# SkateRemote.net
KiCad netlist of a schematic drawn in EAGLE
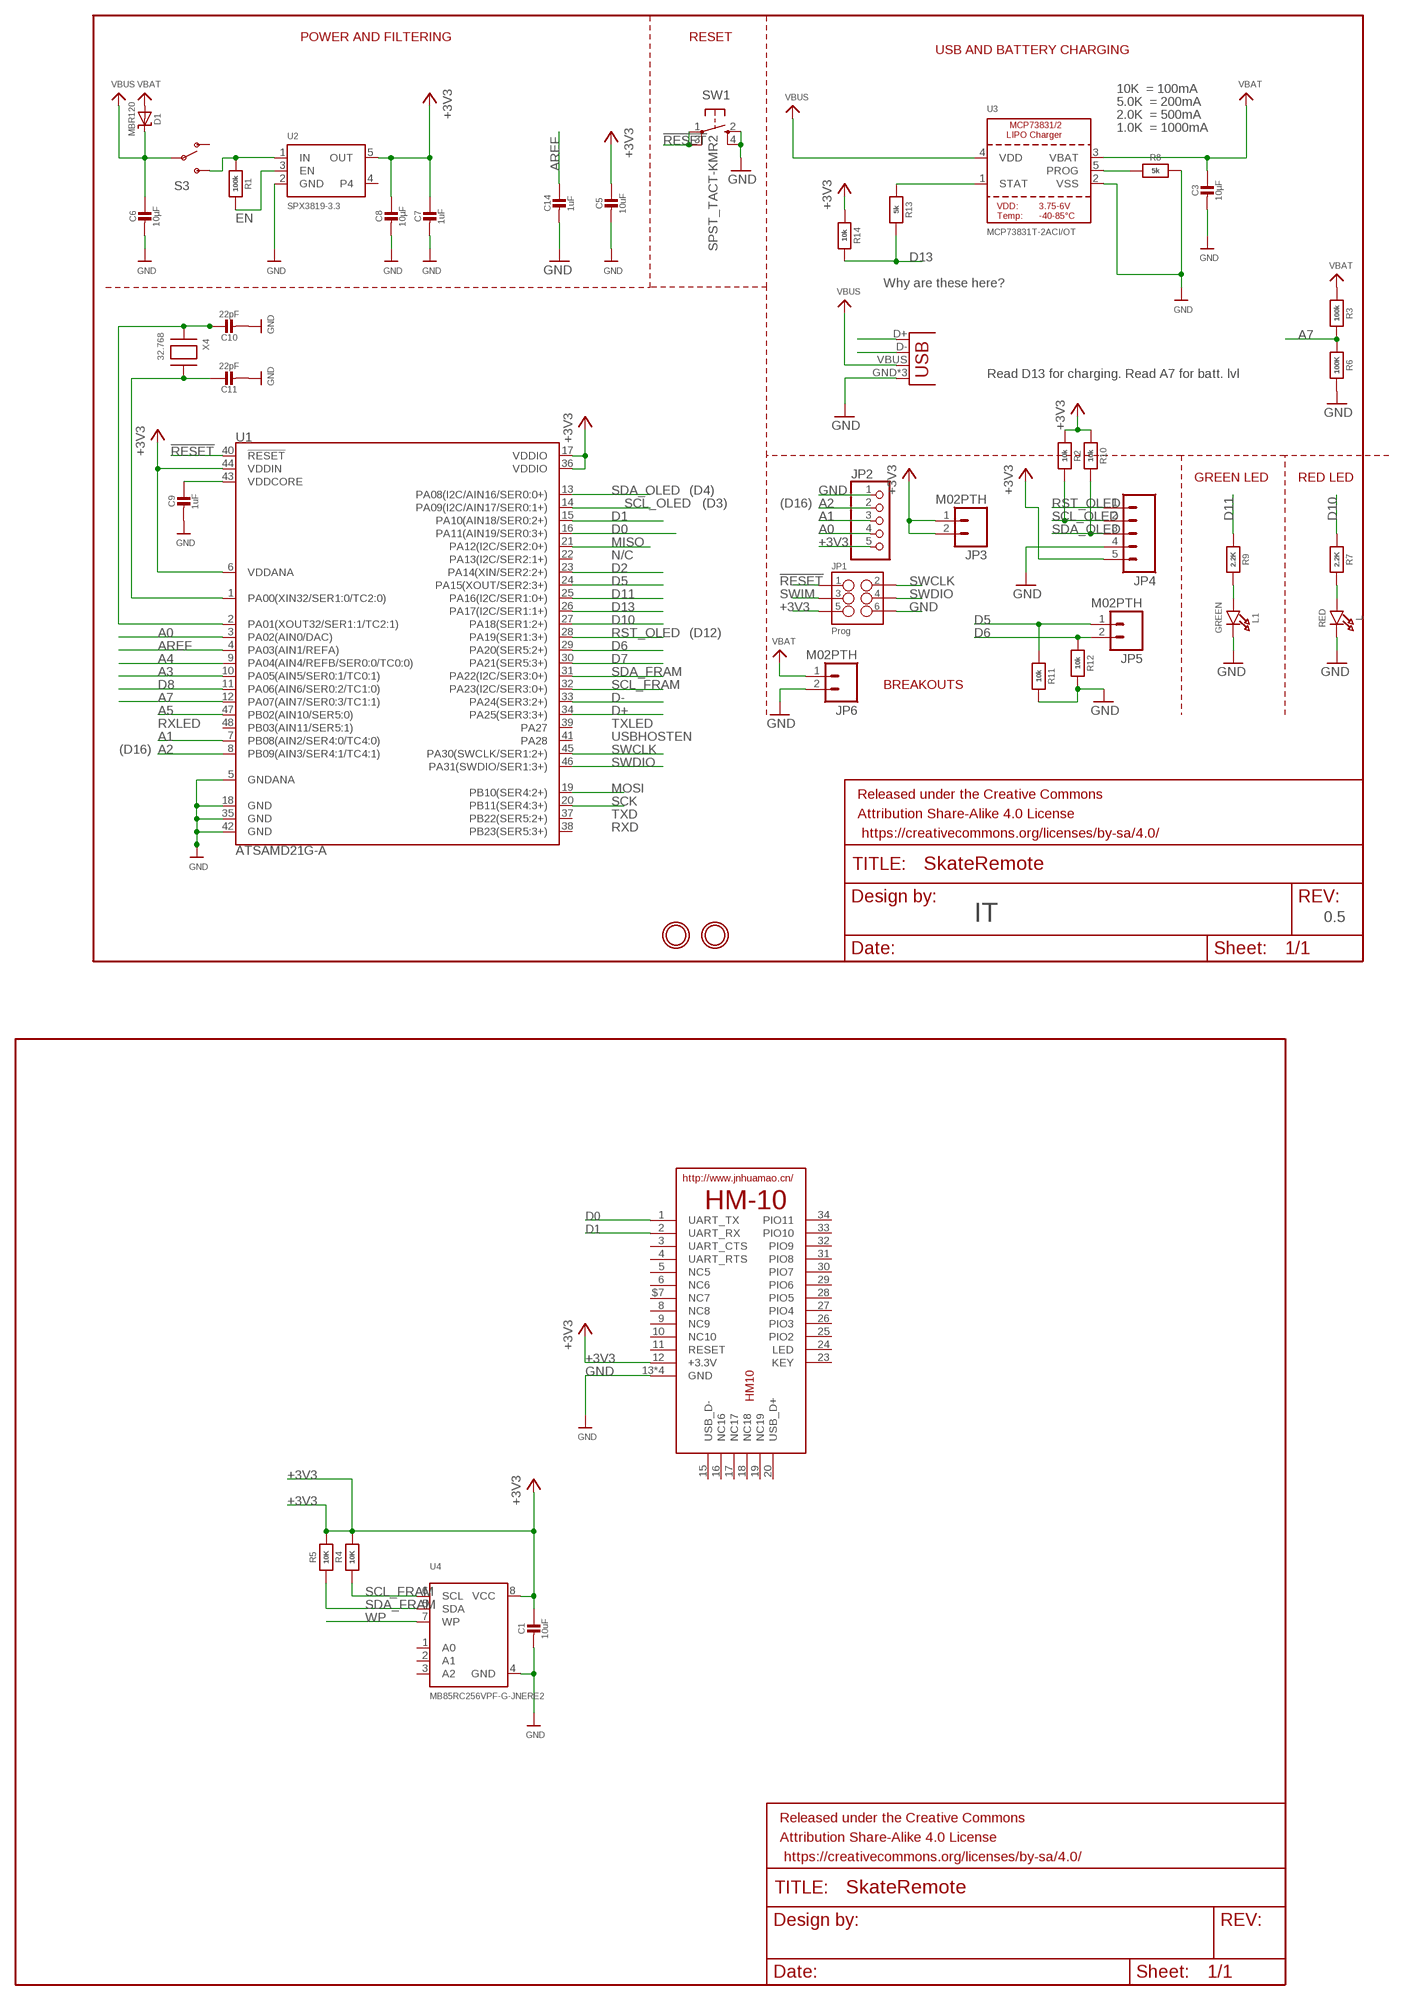
[diagram p0: schematic, sheet 1]

(export (version "E")
  (design (tool "Eeschema 10.0.6"))
  (components
    (comp (ref "C1")
      (value "10uF")
      (footprint "eagle-import:_0805MP")
      (libsource (lib "eagle-import") (part "CAP_CERAMIC_0805MP"))
    )
    (comp (ref "C3")
      (value "10µF")
      (footprint "eagle-import:0805-NO")
      (libsource (lib "eagle-import") (part "CAP_CERAMIC0805-NOOUTLINE"))
    )
    (comp (ref "C5")
      (value "10uF")
      (footprint "eagle-import:0805-NO")
      (libsource (lib "eagle-import") (part "CAP_CERAMIC0805-NOOUTLINE"))
    )
    (comp (ref "C6")
      (value "10µF")
      (footprint "eagle-import:0805-NO")
      (libsource (lib "eagle-import") (part "CAP_CERAMIC0805-NOOUTLINE"))
    )
    (comp (ref "C7")
      (value "1uF")
      (footprint "eagle-import:0805-NO")
      (libsource (lib "eagle-import") (part "CAP_CERAMIC0805-NOOUTLINE"))
    )
    (comp (ref "C8")
      (value "10µF")
      (footprint "eagle-import:0805-NO")
      (libsource (lib "eagle-import") (part "CAP_CERAMIC0805-NOOUTLINE"))
    )
    (comp (ref "C9")
      (value "1uF")
      (footprint "eagle-import:0805-NO")
      (libsource (lib "eagle-import") (part "CAP_CERAMIC0805-NOOUTLINE"))
    )
    (comp (ref "C10")
      (value "22pF")
      (footprint "eagle-import:0805-NO")
      (libsource (lib "eagle-import") (part "CAP_CERAMIC0805-NOOUTLINE"))
    )
    (comp (ref "C11")
      (value "22pF")
      (footprint "eagle-import:0805-NO")
      (libsource (lib "eagle-import") (part "CAP_CERAMIC0805-NOOUTLINE"))
    )
    (comp (ref "C14")
      (value "1uF")
      (footprint "eagle-import:0805-NO")
      (libsource (lib "eagle-import") (part "CAP_CERAMIC0805-NOOUTLINE"))
    )
    (comp (ref "D1")
      (value "MBR120")
      (footprint "eagle-import:SOD-123")
      (libsource (lib "eagle-import") (part "DIODE-SCHOTTKYSOD-123"))
    )
    (comp (ref "FRAME2")
      (value "FRAME-LETTER")
      (footprint "eagle-import:CREATIVE_COMMONS")
      (libsource (lib "eagle-import") (part "FRAME-LETTER"))
    )
    (comp (ref "FRAME3")
      (value "FRAME-LETTER")
      (footprint "eagle-import:CREATIVE_COMMONS")
      (libsource (lib "eagle-import") (part "FRAME-LETTER"))
    )
    (comp (ref "HM10")
      (value "HM-10-BOARD")
      (footprint "eagle-import:26.9X13X2.2_BOARD")
      (libsource (lib "eagle-import") (part "HM-10-BOARD"))
    )
    (comp (ref "JP1")
      (value "Prog")
      (footprint "eagle-import:2X3")
      (libsource (lib "eagle-import") (part "M03X22X3_SILK_MALE_PTH"))
    )
    (comp (ref "JP2")
      (value "PINHD-1X5")
      (footprint "eagle-import:1X05")
      (libsource (lib "eagle-import") (part "PINHD-1X5"))
    )
    (comp (ref "JP3")
      (value "M02PTH")
      (footprint "eagle-import:1X02")
      (libsource (lib "eagle-import") (part "M02PTH"))
    )
    (comp (ref "JP4")
      (value "M05PTH")
      (footprint "eagle-import:1X05")
      (libsource (lib "eagle-import") (part "M05PTH"))
    )
    (comp (ref "JP5")
      (value "M02PTH")
      (footprint "eagle-import:1X02")
      (libsource (lib "eagle-import") (part "M02PTH"))
    )
    (comp (ref "JP6")
      (value "M02PTH")
      (footprint "eagle-import:1X02")
      (libsource (lib "eagle-import") (part "M02PTH"))
    )
    (comp (ref "L")
      (value "RED")
      (footprint "eagle-import:CHIPLED_0805_NOOUTLINE")
      (libsource (lib "eagle-import") (part "LED0805_NOOUTLINE"))
    )
    (comp (ref "L1")
      (value "GREEN")
      (footprint "eagle-import:CHIPLED_0805_NOOUTLINE")
      (libsource (lib "eagle-import") (part "LED0805_NOOUTLINE"))
    )
    (comp (ref "R1")
      (value "100k")
      (footprint "eagle-import:0805-NO")
      (libsource (lib "eagle-import") (part "RESISTOR0805_NOOUTLINE"))
    )
    (comp (ref "R2")
      (value "10k")
      (footprint "eagle-import:0805-NO")
      (libsource (lib "eagle-import") (part "RESISTOR0805_NOOUTLINE"))
    )
    (comp (ref "R3")
      (value "100k")
      (footprint "eagle-import:0805-NO")
      (libsource (lib "eagle-import") (part "RESISTOR0805_NOOUTLINE"))
    )
    (comp (ref "R4")
      (value "10K")
      (footprint "eagle-import:_0805MP")
      (libsource (lib "eagle-import") (part "RESISTOR_0805MP"))
    )
    (comp (ref "R5")
      (value "10K")
      (footprint "eagle-import:_0805MP")
      (libsource (lib "eagle-import") (part "RESISTOR_0805MP"))
    )
    (comp (ref "R6")
      (value "100K")
      (footprint "eagle-import:0805-NO")
      (libsource (lib "eagle-import") (part "RESISTOR0805_NOOUTLINE"))
    )
    (comp (ref "R7")
      (value "2.2K")
      (footprint "eagle-import:0805-NO")
      (libsource (lib "eagle-import") (part "RESISTOR0805_NOOUTLINE"))
    )
    (comp (ref "R8")
      (value "5k")
      (footprint "eagle-import:0805-NO")
      (libsource (lib "eagle-import") (part "RESISTOR0805_NOOUTLINE"))
    )
    (comp (ref "R9")
      (value "2.2K")
      (footprint "eagle-import:0805-NO")
      (libsource (lib "eagle-import") (part "RESISTOR0805_NOOUTLINE"))
    )
    (comp (ref "R10")
      (value "10k")
      (footprint "eagle-import:0805-NO")
      (libsource (lib "eagle-import") (part "RESISTOR0805_NOOUTLINE"))
    )
    (comp (ref "R11")
      (value "10k")
      (footprint "eagle-import:0805-NO")
      (libsource (lib "eagle-import") (part "RESISTOR0805_NOOUTLINE"))
    )
    (comp (ref "R12")
      (value "10k")
      (footprint "eagle-import:0805-NO")
      (libsource (lib "eagle-import") (part "RESISTOR0805_NOOUTLINE"))
    )
    (comp (ref "R13")
      (value "5k")
      (footprint "eagle-import:0805-NO")
      (libsource (lib "eagle-import") (part "RESISTOR0805_NOOUTLINE"))
    )
    (comp (ref "R14")
      (value "10k")
      (footprint "eagle-import:0805-NO")
      (libsource (lib "eagle-import") (part "RESISTOR0805_NOOUTLINE"))
    )
    (comp (ref "S3")
      (value "SWITCH-SPDT-SMD-A")
      (footprint "eagle-import:SWITCH-SPST-SMD-A")
      (libsource (lib "eagle-import") (part "SWITCH-SPDT-SMD-A"))
    )
    (comp (ref "SW1")
      (value "SPST_TACT-KMR2")
      (footprint "eagle-import:KMR2")
      (libsource (lib "eagle-import") (part "SPST_TACT-KMR2"))
    )
    (comp (ref "U$31")
      (value "MOUNTINGHOLE2.5")
      (footprint "eagle-import:MOUNTINGHOLE_2.5_PLATED")
      (libsource (lib "eagle-import") (part "MOUNTINGHOLE2.5"))
    )
    (comp (ref "U$32")
      (value "MOUNTINGHOLE2.5")
      (footprint "eagle-import:MOUNTINGHOLE_2.5_PLATED")
      (libsource (lib "eagle-import") (part "MOUNTINGHOLE2.5"))
    )
    (comp (ref "U1")
      (value "ATSAMD21G-A")
      (footprint "eagle-import:TQFP-48")
      (libsource (lib "eagle-import") (part "ATSAMD21G-A"))
    )
    (comp (ref "U2")
      (value "SPX3819-3.3")
      (footprint "eagle-import:SOT23-5")
      (libsource (lib "eagle-import") (part "VREG_SOT23-5"))
    )
    (comp (ref "U3")
      (value "MCP73831T-2ACI/OT")
      (footprint "eagle-import:SOT23-5")
      (libsource (lib "eagle-import") (part "MCP73831/2"))
    )
    (comp (ref "U4")
      (value "MB85RC256VPF-G-JNERE2")
      (footprint "eagle-import:SOIC8_208MIL")
      (libsource (lib "eagle-import") (part "FRAM_SOIC8_I2C"))
    )
    (comp (ref "X3")
      (value "microUSB")
      (footprint "eagle-import:USB-MICROB")
      (libsource (lib "eagle-import") (part "USB-MICROB"))
    )
    (comp (ref "X4")
      (value "32.768")
      (footprint "eagle-import:XTAL3215")
      (libsource (lib "eagle-import") (part "XTAL-3.2X1.5"))
    )
  )
  (nets
    (net (code "1") (name "+3V3") (class "Default")
      (node (ref "C1") (pin "1") (pinfunction "1_1") (pintype "passive"))
      (node (ref "C5") (pin "1") (pinfunction "1_1") (pintype "passive"))
      (node (ref "C7") (pin "1") (pinfunction "1_1") (pintype "passive"))
      (node (ref "C8") (pin "1") (pinfunction "1_1") (pintype "passive"))
      (node (ref "HM10") (pin "12") (pinfunction "+3.3V_12") (pintype "bidirectional"))
      (node (ref "JP1") (pin "5") (pinfunction "5_5") (pintype "bidirectional"))
      (node (ref "JP2") (pin "5") (pinfunction "5_5") (pintype "passive"))
      (node (ref "JP3") (pin "1") (pinfunction "1_1") (pintype "passive"))
      (node (ref "JP3") (pin "2") (pinfunction "2_2") (pintype "passive"))
      (node (ref "JP4") (pin "5") (pinfunction "5_5") (pintype "passive"))
      (node (ref "R10") (pin "1") (pinfunction "1_1") (pintype "passive"))
      (node (ref "R14") (pin "1") (pinfunction "1_1") (pintype "passive"))
      (node (ref "R2") (pin "1") (pinfunction "1_1") (pintype "passive"))
      (node (ref "R4") (pin "2") (pinfunction "2_2") (pintype "passive"))
      (node (ref "R5") (pin "2") (pinfunction "2_2") (pintype "passive"))
      (node (ref "U1") (pin "17") (pinfunction "VDDIO_17") (pintype "bidirectional"))
      (node (ref "U1") (pin "36") (pinfunction "VDDIO_36") (pintype "bidirectional"))
      (node (ref "U1") (pin "44") (pinfunction "VDDIN_44") (pintype "bidirectional"))
      (node (ref "U1") (pin "6") (pinfunction "VDDANA_6") (pintype "bidirectional"))
      (node (ref "U2") (pin "5") (pinfunction "OUT_5") (pintype "power_in"))
      (node (ref "U4") (pin "8") (pinfunction "VCC_8") (pintype "power_in"))
    )
    (net (code "2") (name "/A0") (class "Default")
      (node (ref "JP2") (pin "4") (pinfunction "4_4") (pintype "passive"))
      (node (ref "U1") (pin "3") (pinfunction "PA02(AIN0/DAC)_3") (pintype "bidirectional"))
    )
    (net (code "3") (name "/A1") (class "Default")
      (node (ref "JP2") (pin "3") (pinfunction "3_3") (pintype "passive"))
      (node (ref "U1") (pin "7") (pinfunction "PB08(AIN2/SER4:0/TC4:0)_7") (pintype "bidirectional"))
    )
    (net (code "4") (name "/A2") (class "Default")
      (node (ref "JP2") (pin "2") (pinfunction "2_2") (pintype "passive"))
      (node (ref "U1") (pin "8") (pinfunction "PB09(AIN3/SER4:1/TC4:1)_8") (pintype "bidirectional"))
    )
    (net (code "5") (name "/A3") (class "Default")
      (node (ref "U1") (pin "10") (pinfunction "PA05(AIN5/SER0:1/TC0:1)_10") (pintype "bidirectional"))
    )
    (net (code "6") (name "/A4") (class "Default")
      (node (ref "U1") (pin "9") (pinfunction "PA04(AIN4/REFB/SER0:0/TC0:0)_9") (pintype "bidirectional"))
    )
    (net (code "7") (name "/A5") (class "Default")
      (node (ref "U1") (pin "47") (pinfunction "PB02(AIN10/SER5:0)_47") (pintype "bidirectional"))
    )
    (net (code "8") (name "/A7") (class "Default")
      (node (ref "R3") (pin "2") (pinfunction "2_2") (pintype "passive"))
      (node (ref "R6") (pin "1") (pinfunction "1_1") (pintype "passive"))
      (node (ref "U1") (pin "12") (pinfunction "PA07(AIN7/SER0:3/TC1:1)_12") (pintype "bidirectional"))
    )
    (net (code "9") (name "/AREF") (class "Default")
      (node (ref "C14") (pin "1") (pinfunction "1_1") (pintype "passive"))
      (node (ref "U1") (pin "4") (pinfunction "PA03(AIN1/REFA)_4") (pintype "bidirectional"))
    )
    (net (code "10") (name "/D+") (class "Default")
      (node (ref "U1") (pin "34") (pinfunction "PA25(SER3:3+)_34") (pintype "bidirectional"))
      (node (ref "X3") (pin "D+") (pinfunction "D+_D+") (pintype "bidirectional"))
    )
    (net (code "11") (name "/D-") (class "Default")
      (node (ref "U1") (pin "33") (pinfunction "PA24(SER3:2+)_33") (pintype "bidirectional"))
      (node (ref "X3") (pin "D-") (pinfunction "D-_D-") (pintype "bidirectional"))
    )
    (net (code "12") (name "/D0") (class "Default")
      (node (ref "HM10") (pin "1") (pinfunction "UART_TX_1") (pintype "bidirectional"))
      (node (ref "U1") (pin "16") (pinfunction "PA11(AIN19/SER0:3+)_16") (pintype "bidirectional"))
    )
    (net (code "13") (name "/D1") (class "Default")
      (node (ref "HM10") (pin "2") (pinfunction "UART_RX_2") (pintype "bidirectional"))
      (node (ref "U1") (pin "15") (pinfunction "PA10(AIN18/SER0:2+)_15") (pintype "bidirectional"))
    )
    (net (code "14") (name "/D2") (class "Default")
      (node (ref "U1") (pin "23") (pinfunction "PA14(XIN/SER2:2+)_23") (pintype "bidirectional"))
    )
    (net (code "15") (name "/D5") (class "Default")
      (node (ref "JP5") (pin "1") (pinfunction "1_1") (pintype "passive"))
      (node (ref "R11") (pin "1") (pinfunction "1_1") (pintype "passive"))
      (node (ref "U1") (pin "24") (pinfunction "PA15(XOUT/SER2:3+)_24") (pintype "bidirectional"))
    )
    (net (code "16") (name "/D6") (class "Default")
      (node (ref "JP5") (pin "2") (pinfunction "2_2") (pintype "passive"))
      (node (ref "R12") (pin "1") (pinfunction "1_1") (pintype "passive"))
      (node (ref "U1") (pin "29") (pinfunction "PA20(SER5:2+)_29") (pintype "bidirectional"))
    )
    (net (code "17") (name "/D7") (class "Default")
      (node (ref "U1") (pin "30") (pinfunction "PA21(SER5:3+)_30") (pintype "bidirectional"))
    )
    (net (code "18") (name "/D8") (class "Default")
      (node (ref "U1") (pin "11") (pinfunction "PA06(AIN6/SER0:2/TC1:0)_11") (pintype "bidirectional"))
    )
    (net (code "19") (name "/D10") (class "Default")
      (node (ref "R7") (pin "1") (pinfunction "1_1") (pintype "passive"))
      (node (ref "U1") (pin "27") (pinfunction "PA18(SER1:2+)_27") (pintype "bidirectional"))
    )
    (net (code "20") (name "/D11") (class "Default")
      (node (ref "R9") (pin "1") (pinfunction "1_1") (pintype "passive"))
      (node (ref "U1") (pin "25") (pinfunction "PA16(I2C/SER1:0+)_25") (pintype "bidirectional"))
    )
    (net (code "21") (name "/D13") (class "Default")
      (node (ref "R13") (pin "2") (pinfunction "2_2") (pintype "passive"))
      (node (ref "R14") (pin "2") (pinfunction "2_2") (pintype "passive"))
      (node (ref "U1") (pin "26") (pinfunction "PA17(I2C/SER1:1+)_26") (pintype "bidirectional"))
    )
    (net (code "22") (name "/EN") (class "Default")
      (node (ref "R1") (pin "2") (pinfunction "2_2") (pintype "passive"))
      (node (ref "U2") (pin "3") (pinfunction "EN_3") (pintype "input"))
    )
    (net (code "23") (name "/MISO") (class "Default")
      (node (ref "U1") (pin "21") (pinfunction "PA12(I2C/SER2:0+)_21") (pintype "bidirectional"))
    )
    (net (code "24") (name "/MOSI") (class "Default")
      (node (ref "U1") (pin "19") (pinfunction "PB10(SER4:2+)_19") (pintype "bidirectional"))
    )
    (net (code "25") (name "/RST_OLED") (class "Default")
      (node (ref "JP4") (pin "1") (pinfunction "1_1") (pintype "passive"))
      (node (ref "U1") (pin "28") (pinfunction "PA19(SER1:3+)_28") (pintype "bidirectional"))
    )
    (net (code "26") (name "/SCK") (class "Default")
      (node (ref "U1") (pin "20") (pinfunction "PB11(SER4:3+)_20") (pintype "bidirectional"))
    )
    (net (code "27") (name "/SCL_FRAM") (class "Default")
      (node (ref "R4") (pin "1") (pinfunction "1_1") (pintype "passive"))
      (node (ref "U1") (pin "32") (pinfunction "PA23(I2C/SER3:0+)_32") (pintype "bidirectional"))
      (node (ref "U4") (pin "6") (pinfunction "SCL_6") (pintype "input"))
    )
    (net (code "28") (name "/SCL_OLED") (class "Default")
      (node (ref "JP4") (pin "2") (pinfunction "2_2") (pintype "passive"))
      (node (ref "R2") (pin "2") (pinfunction "2_2") (pintype "passive"))
      (node (ref "U1") (pin "14") (pinfunction "PA09(I2C/AIN17/SER0:1+)_14") (pintype "bidirectional"))
    )
    (net (code "29") (name "/SDA_FRAM") (class "Default")
      (node (ref "R5") (pin "1") (pinfunction "1_1") (pintype "passive"))
      (node (ref "U1") (pin "31") (pinfunction "PA22(I2C/SER3:0+)_31") (pintype "bidirectional"))
      (node (ref "U4") (pin "5") (pinfunction "SDA_5") (pintype "bidirectional"))
    )
    (net (code "30") (name "/SDA_OLED") (class "Default")
      (node (ref "JP4") (pin "3") (pinfunction "3_3") (pintype "passive"))
      (node (ref "R10") (pin "2") (pinfunction "2_2") (pintype "passive"))
      (node (ref "U1") (pin "13") (pinfunction "PA08(I2C/AIN16/SER0:0+)_13") (pintype "bidirectional"))
    )
    (net (code "31") (name "/SWCLK") (class "Default")
      (node (ref "JP1") (pin "2") (pinfunction "2_2") (pintype "bidirectional"))
      (node (ref "U1") (pin "45") (pinfunction "PA30(SWCLK/SER1:2+)_45") (pintype "bidirectional"))
    )
    (net (code "32") (name "/SWDIO") (class "Default")
      (node (ref "JP1") (pin "4") (pinfunction "4_4") (pintype "bidirectional"))
      (node (ref "U1") (pin "46") (pinfunction "PA31(SWDIO/SER1:3+)_46") (pintype "bidirectional"))
    )
    (net (code "33") (name "/SWIM") (class "Default")
      (node (ref "JP1") (pin "3") (pinfunction "3_3") (pintype "bidirectional"))
    )
    (net (code "34") (name "/WP") (class "Default")
      (node (ref "U4") (pin "7") (pinfunction "WP_7") (pintype "input"))
    )
    (net (code "35") (name "/~{RESET}") (class "Default")
      (node (ref "JP1") (pin "1") (pinfunction "1_1") (pintype "bidirectional"))
      (node (ref "SW1") (pin "1") (pinfunction "P_1") (pintype "passive"))
      (node (ref "SW1") (pin "3") (pinfunction "P1_3") (pintype "passive"))
      (node (ref "U1") (pin "40") (pinfunction "~{RESET}_40") (pintype "bidirectional"))
    )
    (net (code "36") (name "GND") (class "Default")
      (node (ref "C1") (pin "2") (pinfunction "2_2") (pintype "passive"))
      (node (ref "C10") (pin "2") (pinfunction "2_2") (pintype "passive"))
      (node (ref "C11") (pin "2") (pinfunction "2_2") (pintype "passive"))
      (node (ref "C14") (pin "2") (pinfunction "2_2") (pintype "passive"))
      (node (ref "C3") (pin "2") (pinfunction "2_2") (pintype "passive"))
      (node (ref "C5") (pin "2") (pinfunction "2_2") (pintype "passive"))
      (node (ref "C6") (pin "2") (pinfunction "2_2") (pintype "passive"))
      (node (ref "C7") (pin "2") (pinfunction "2_2") (pintype "passive"))
      (node (ref "C8") (pin "2") (pinfunction "2_2") (pintype "passive"))
      (node (ref "C9") (pin "2") (pinfunction "2_2") (pintype "passive"))
      (node (ref "HM10") (pin "13") (pinfunction "GND_13") (pintype "bidirectional"))
      (node (ref "HM10") (pin "14") (pinfunction "GND_14") (pintype "bidirectional"))
      (node (ref "HM10") (pin "21") (pinfunction "GND_21") (pintype "bidirectional"))
      (node (ref "HM10") (pin "22") (pinfunction "GND_22") (pintype "bidirectional"))
      (node (ref "JP1") (pin "6") (pinfunction "6_6") (pintype "bidirectional"))
      (node (ref "JP2") (pin "1") (pinfunction "1_1") (pintype "passive"))
      (node (ref "JP4") (pin "4") (pinfunction "4_4") (pintype "passive"))
      (node (ref "JP6") (pin "2") (pinfunction "2_2") (pintype "passive"))
      (node (ref "L") (pin "C") (pinfunction "C_C") (pintype "passive"))
      (node (ref "L1") (pin "C") (pinfunction "C_C") (pintype "passive"))
      (node (ref "R11") (pin "2") (pinfunction "2_2") (pintype "passive"))
      (node (ref "R12") (pin "2") (pinfunction "2_2") (pintype "passive"))
      (node (ref "R6") (pin "2") (pinfunction "2_2") (pintype "passive"))
      (node (ref "R8") (pin "2") (pinfunction "2_2") (pintype "passive"))
      (node (ref "SW1") (pin "2") (pinfunction "S_2") (pintype "passive"))
      (node (ref "SW1") (pin "4") (pinfunction "S1_4") (pintype "passive"))
      (node (ref "U1") (pin "18") (pinfunction "GND_18") (pintype "bidirectional"))
      (node (ref "U1") (pin "35") (pinfunction "GND_35") (pintype "bidirectional"))
      (node (ref "U1") (pin "42") (pinfunction "GND_42") (pintype "bidirectional"))
      (node (ref "U1") (pin "5") (pinfunction "GNDANA_5") (pintype "bidirectional"))
      (node (ref "U2") (pin "2") (pinfunction "GND_2") (pintype "power_in"))
      (node (ref "U3") (pin "2") (pinfunction "VSS_2") (pintype "power_in"))
      (node (ref "U4") (pin "4") (pinfunction "GND_4") (pintype "power_in"))
      (node (ref "X3") (pin "GND") (pinfunction "GND_GND") (pintype "bidirectional"))
      (node (ref "X3") (pin "MT1") (pinfunction "GND_MT1") (pintype "bidirectional"))
      (node (ref "X3") (pin "MT2") (pinfunction "GND_MT2") (pintype "bidirectional"))
    )
    (net (code "37") (name "Net-(L-PadA)") (class "Default")
      (node (ref "L") (pin "A") (pinfunction "A_A") (pintype "passive"))
      (node (ref "R7") (pin "2") (pinfunction "2_2") (pintype "passive"))
    )
    (net (code "38") (name "Net-(L1-PadA)") (class "Default")
      (node (ref "L1") (pin "A") (pinfunction "A_A") (pintype "passive"))
      (node (ref "R9") (pin "2") (pinfunction "2_2") (pintype "passive"))
    )
    (net (code "39") (name "Net-(S3-S)") (class "Default")
      (node (ref "R1") (pin "1") (pinfunction "1_1") (pintype "passive"))
      (node (ref "S3") (pin "3") (pinfunction "S_3") (pintype "passive"))
      (node (ref "U2") (pin "1") (pinfunction "IN_1") (pintype "power_in"))
    )
    (net (code "40") (name "Net-(U1-PA00(XIN32{slash}SER1:0{slash}TC2:0))") (class "Default")
      (node (ref "C11") (pin "1") (pinfunction "1_1") (pintype "passive"))
      (node (ref "U1") (pin "1") (pinfunction "PA00(XIN32/SER1:0/TC2:0)_1") (pintype "bidirectional"))
      (node (ref "X4") (pin "P$2") (pinfunction "P$2_P$2") (pintype "bidirectional"))
    )
    (net (code "41") (name "Net-(U1-PA01(XOUT32{slash}SER1:1{slash}TC2:1))") (class "Default")
      (node (ref "C10") (pin "1") (pinfunction "1_1") (pintype "passive"))
      (node (ref "U1") (pin "2") (pinfunction "PA01(XOUT32/SER1:1/TC2:1)_2") (pintype "bidirectional"))
      (node (ref "X4") (pin "P$1") (pinfunction "P$1_P$1") (pintype "bidirectional"))
    )
    (net (code "42") (name "Net-(U1-VDDCORE)") (class "Default")
      (node (ref "C9") (pin "1") (pinfunction "1_1") (pintype "passive"))
      (node (ref "U1") (pin "43") (pinfunction "VDDCORE_43") (pintype "bidirectional"))
    )
    (net (code "43") (name "Net-(U3-PROG)") (class "Default")
      (node (ref "R8") (pin "1") (pinfunction "1_1") (pintype "passive"))
      (node (ref "U3") (pin "5") (pinfunction "PROG_5") (pintype "input"))
    )
    (net (code "44") (name "Net-(U3-STAT)") (class "Default")
      (node (ref "R13") (pin "1") (pinfunction "1_1") (pintype "passive"))
      (node (ref "U3") (pin "1") (pinfunction "STAT_1") (pintype "output"))
    )
    (net (code "45") (name "VBAT") (class "Default")
      (node (ref "C3") (pin "1") (pinfunction "1_1") (pintype "passive"))
      (node (ref "D1") (pin "A") (pinfunction "A_A") (pintype "passive"))
      (node (ref "JP6") (pin "1") (pinfunction "1_1") (pintype "passive"))
      (node (ref "R3") (pin "1") (pinfunction "1_1") (pintype "passive"))
      (node (ref "U3") (pin "3") (pinfunction "VBAT_3") (pintype "power_in"))
    )
    (net (code "46") (name "VBUS") (class "Default")
      (node (ref "C6") (pin "1") (pinfunction "1_1") (pintype "passive"))
      (node (ref "D1") (pin "C") (pinfunction "C_C") (pintype "passive"))
      (node (ref "S3") (pin "2") (pinfunction "P_2") (pintype "passive"))
      (node (ref "U3") (pin "4") (pinfunction "VDD_4") (pintype "power_in"))
      (node (ref "X3") (pin "VBUS") (pinfunction "VBUS_VBUS") (pintype "bidirectional"))
    )
    (net (code "47") (name "unconnected-(HM10-KEY-Pad23)") (class "Default")
      (node (ref "HM10") (pin "23") (pinfunction "KEY_23") (pintype "bidirectional"))
    )
    (net (code "48") (name "unconnected-(HM10-LED-Pad24)") (class "Default")
      (node (ref "HM10") (pin "24") (pinfunction "LED_24") (pintype "bidirectional"))
    )
    (net (code "49") (name "unconnected-(HM10-NC5-Pad5)") (class "Default")
      (node (ref "HM10") (pin "5") (pinfunction "NC5_5") (pintype "bidirectional"))
    )
    (net (code "50") (name "unconnected-(HM10-NC6-Pad6)") (class "Default")
      (node (ref "HM10") (pin "6") (pinfunction "NC6_6") (pintype "bidirectional"))
    )
    (net (code "51") (name "unconnected-(HM10-NC7-Pad$7)") (class "Default")
      (node (ref "HM10") (pin "$7") (pinfunction "NC7_$7") (pintype "bidirectional"))
    )
    (net (code "52") (name "unconnected-(HM10-NC8-Pad8)") (class "Default")
      (node (ref "HM10") (pin "8") (pinfunction "NC8_8") (pintype "bidirectional"))
    )
    (net (code "53") (name "unconnected-(HM10-NC9-Pad9)") (class "Default")
      (node (ref "HM10") (pin "9") (pinfunction "NC9_9") (pintype "bidirectional"))
    )
    (net (code "54") (name "unconnected-(HM10-NC10-Pad10)") (class "Default")
      (node (ref "HM10") (pin "10") (pinfunction "NC10_10") (pintype "bidirectional"))
    )
    (net (code "55") (name "unconnected-(HM10-NC16-Pad16)") (class "Default")
      (node (ref "HM10") (pin "16") (pinfunction "NC16_16") (pintype "bidirectional"))
    )
    (net (code "56") (name "unconnected-(HM10-NC17-Pad17)") (class "Default")
      (node (ref "HM10") (pin "17") (pinfunction "NC17_17") (pintype "bidirectional"))
    )
    (net (code "57") (name "unconnected-(HM10-NC18-Pad18)") (class "Default")
      (node (ref "HM10") (pin "18") (pinfunction "NC18_18") (pintype "bidirectional"))
    )
    (net (code "58") (name "unconnected-(HM10-NC19-Pad19)") (class "Default")
      (node (ref "HM10") (pin "19") (pinfunction "NC19_19") (pintype "bidirectional"))
    )
    (net (code "59") (name "unconnected-(HM10-PIO2-Pad25)") (class "Default")
      (node (ref "HM10") (pin "25") (pinfunction "PIO2_25") (pintype "bidirectional"))
    )
    (net (code "60") (name "unconnected-(HM10-PIO3-Pad26)") (class "Default")
      (node (ref "HM10") (pin "26") (pinfunction "PIO3_26") (pintype "bidirectional"))
    )
    (net (code "61") (name "unconnected-(HM10-PIO4-Pad27)") (class "Default")
      (node (ref "HM10") (pin "27") (pinfunction "PIO4_27") (pintype "bidirectional"))
    )
    (net (code "62") (name "unconnected-(HM10-PIO5-Pad28)") (class "Default")
      (node (ref "HM10") (pin "28") (pinfunction "PIO5_28") (pintype "bidirectional"))
    )
    (net (code "63") (name "unconnected-(HM10-PIO6-Pad29)") (class "Default")
      (node (ref "HM10") (pin "29") (pinfunction "PIO6_29") (pintype "bidirectional"))
    )
    (net (code "64") (name "unconnected-(HM10-PIO7-Pad30)") (class "Default")
      (node (ref "HM10") (pin "30") (pinfunction "PIO7_30") (pintype "bidirectional"))
    )
    (net (code "65") (name "unconnected-(HM10-PIO8-Pad31)") (class "Default")
      (node (ref "HM10") (pin "31") (pinfunction "PIO8_31") (pintype "bidirectional"))
    )
    (net (code "66") (name "unconnected-(HM10-PIO9-Pad32)") (class "Default")
      (node (ref "HM10") (pin "32") (pinfunction "PIO9_32") (pintype "bidirectional"))
    )
    (net (code "67") (name "unconnected-(HM10-PIO10-Pad33)") (class "Default")
      (node (ref "HM10") (pin "33") (pinfunction "PIO10_33") (pintype "bidirectional"))
    )
    (net (code "68") (name "unconnected-(HM10-PIO11-Pad34)") (class "Default")
      (node (ref "HM10") (pin "34") (pinfunction "PIO11_34") (pintype "bidirectional"))
    )
    (net (code "69") (name "unconnected-(HM10-RESET-Pad11)") (class "Default")
      (node (ref "HM10") (pin "11") (pinfunction "RESET_11") (pintype "bidirectional"))
    )
    (net (code "70") (name "unconnected-(HM10-UART_CTS-Pad3)") (class "Default")
      (node (ref "HM10") (pin "3") (pinfunction "UART_CTS_3") (pintype "bidirectional"))
    )
    (net (code "71") (name "unconnected-(HM10-UART_RTS-Pad4)") (class "Default")
      (node (ref "HM10") (pin "4") (pinfunction "UART_RTS_4") (pintype "bidirectional"))
    )
    (net (code "72") (name "unconnected-(HM10-USB_D+-Pad20)") (class "Default")
      (node (ref "HM10") (pin "20") (pinfunction "USB_D+_20") (pintype "bidirectional"))
    )
    (net (code "73") (name "unconnected-(HM10-USB_D--Pad15)") (class "Default")
      (node (ref "HM10") (pin "15") (pinfunction "USB_D-_15") (pintype "bidirectional"))
    )
    (net (code "74") (name "unconnected-(S3-O-Pad1)") (class "Default")
      (node (ref "S3") (pin "1") (pinfunction "O_1") (pintype "passive"))
    )
    (net (code "75") (name "unconnected-(U1-PA13(I2C{slash}SER2:1+)-Pad22)") (class "Default")
      (node (ref "U1") (pin "22") (pinfunction "PA13(I2C/SER2:1+)_22") (pintype "bidirectional"))
    )
    (net (code "76") (name "unconnected-(U1-PA27-Pad39)") (class "Default")
      (node (ref "U1") (pin "39") (pinfunction "PA27_39") (pintype "bidirectional"))
    )
    (net (code "77") (name "unconnected-(U1-PA28-Pad41)") (class "Default")
      (node (ref "U1") (pin "41") (pinfunction "PA28_41") (pintype "bidirectional"))
    )
    (net (code "78") (name "unconnected-(U1-PB03(AIN11{slash}SER5:1)-Pad48)") (class "Default")
      (node (ref "U1") (pin "48") (pinfunction "PB03(AIN11/SER5:1)_48") (pintype "bidirectional"))
    )
    (net (code "79") (name "unconnected-(U1-PB22(SER5:2+)-Pad37)") (class "Default")
      (node (ref "U1") (pin "37") (pinfunction "PB22(SER5:2+)_37") (pintype "bidirectional"))
    )
    (net (code "80") (name "unconnected-(U1-PB23(SER5:3+)-Pad38)") (class "Default")
      (node (ref "U1") (pin "38") (pinfunction "PB23(SER5:3+)_38") (pintype "bidirectional"))
    )
    (net (code "81") (name "unconnected-(U2-P4-Pad4)") (class "Default")
      (node (ref "U2") (pin "4") (pinfunction "P4_4") (pintype "bidirectional"))
    )
    (net (code "82") (name "unconnected-(U4-A0-Pad1)") (class "Default")
      (node (ref "U4") (pin "1") (pinfunction "A0_1") (pintype "input"))
    )
    (net (code "83") (name "unconnected-(U4-A1-Pad2)") (class "Default")
      (node (ref "U4") (pin "2") (pinfunction "A1_2") (pintype "input"))
    )
    (net (code "84") (name "unconnected-(U4-A2-Pad3)") (class "Default")
      (node (ref "U4") (pin "3") (pinfunction "A2_3") (pintype "input"))
    )
  )
)
